# Zigbee_Tracker_v2_Debugger.net
KiCad netlist of a schematic drawn in EAGLE
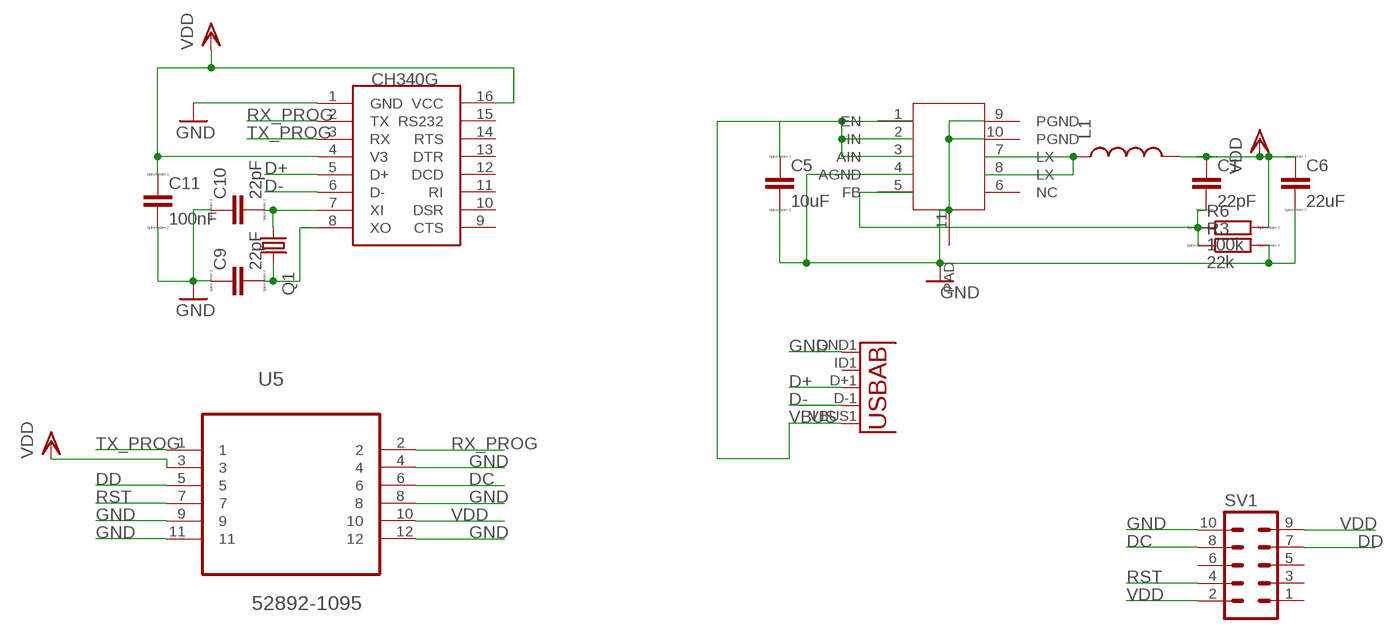
[diagram p0: schematic, sheet 1]

(export (version "E")
  (design (tool "Eeschema 10.0.6"))
  (components
    (comp (ref "C1")
      (value "22pF")
      (footprint "eagle-import:C0402")
      (libsource (lib "eagle-import") (part "CC0402"))
    )
    (comp (ref "C5")
      (value "10uF")
      (footprint "eagle-import:C0402")
      (libsource (lib "eagle-import") (part "CC0402"))
    )
    (comp (ref "C6")
      (value "22uF")
      (footprint "eagle-import:C0402")
      (libsource (lib "eagle-import") (part "CC0402"))
    )
    (comp (ref "C9")
      (value "22pF")
      (footprint "eagle-import:C0402")
      (libsource (lib "eagle-import") (part "CC0402"))
    )
    (comp (ref "C10")
      (value "22pF")
      (footprint "eagle-import:C0402")
      (libsource (lib "eagle-import") (part "CC0402"))
    )
    (comp (ref "C11")
      (value "100nF")
      (footprint "eagle-import:C0402")
      (libsource (lib "eagle-import") (part "CC0402"))
    )
    (comp (ref "L1")
      (value "INDUCTOR")
      (footprint "eagle-import:L0603")
      (libsource (lib "eagle-import") (part "INDUCTOR"))
    )
    (comp (ref "Q1")
      (value "KX-7")
      (footprint "eagle-import:3.2X2.5_KX-7")
      (libsource (lib "eagle-import") (part "KX-7"))
    )
    (comp (ref "R3")
      (value "22k")
      (footprint "eagle-import:R0402")
      (libsource (lib "eagle-import") (part "RR0402"))
    )
    (comp (ref "R6")
      (value "100k")
      (footprint "eagle-import:R0402")
      (libsource (lib "eagle-import") (part "RR0402"))
    )
    (comp (ref "SV1")
      (value "MA05-2")
      (footprint "eagle-import:MA05-2")
      (libsource (lib "eagle-import") (part "MA05-2"))
    )
    (comp (ref "U$1")
      (value "XM5152")
      (footprint "eagle-import:SON50P300X300X80-11T170X240")
      (libsource (lib "eagle-import") (part "XM5152"))
    )
    (comp (ref "U$2")
      (value "CH340G")
      (footprint "eagle-import:SOIC16")
      (libsource (lib "eagle-import") (part "CH340G"))
    )
    (comp (ref "U1")
      (value "USB\"\"")
      (footprint "eagle-import:USB-MICRO-SMD")
      (libsource (lib "eagle-import") (part "USB{dblquote}{dblquote}"))
    )
    (comp (ref "U5")
      (value "52892-1095")
      (footprint "eagle-import:MOLEX_52892-1095")
      (fields (field (name "MF") "Molex"))
      (libsource (lib "eagle-import") (part "52892-1095"))
    )
  )
  (nets
    (net (code "1") (name "/D+") (class "Default")
      (node (ref "U$2") (pin "5") (pinfunction "D+_5") (pintype "bidirectional"))
      (node (ref "U1") (pin "D+1") (pinfunction "D+_D+1") (pintype "bidirectional"))
    )
    (net (code "2") (name "/D-") (class "Default")
      (node (ref "U$2") (pin "6") (pinfunction "D-_6") (pintype "bidirectional"))
      (node (ref "U1") (pin "D-1") (pinfunction "D-_D-1") (pintype "bidirectional"))
    )
    (net (code "3") (name "/DC") (class "Default")
      (node (ref "SV1") (pin "8") (pinfunction "8_8") (pintype "passive"))
      (node (ref "U5") (pin "6") (pinfunction "6_6") (pintype "passive"))
    )
    (net (code "4") (name "/DD") (class "Default")
      (node (ref "SV1") (pin "7") (pinfunction "7_7") (pintype "passive"))
      (node (ref "U5") (pin "5") (pinfunction "5_5") (pintype "passive"))
    )
    (net (code "5") (name "/RST") (class "Default")
      (node (ref "SV1") (pin "4") (pinfunction "4_4") (pintype "passive"))
      (node (ref "U5") (pin "7") (pinfunction "7_7") (pintype "passive"))
    )
    (net (code "6") (name "/RX_PROG") (class "Default")
      (node (ref "U$2") (pin "2") (pinfunction "TX_2") (pintype "bidirectional"))
      (node (ref "U5") (pin "2") (pinfunction "2_2") (pintype "passive"))
    )
    (net (code "7") (name "/TX_PROG") (class "Default")
      (node (ref "U$2") (pin "3") (pinfunction "RX_3") (pintype "bidirectional"))
      (node (ref "U5") (pin "1") (pinfunction "1_1") (pintype "passive"))
    )
    (net (code "8") (name "/VBUS") (class "Default")
      (node (ref "C5") (pin "1") (pinfunction "1_1") (pintype "passive"))
      (node (ref "U$1") (pin "1") (pinfunction "EN_1") (pintype "bidirectional"))
      (node (ref "U$1") (pin "2") (pinfunction "IN_2") (pintype "bidirectional"))
      (node (ref "U$1") (pin "3") (pinfunction "AIN_3") (pintype "bidirectional"))
      (node (ref "U1") (pin "VBUS1") (pinfunction "VBUS_VBUS1") (pintype "bidirectional"))
    )
    (net (code "9") (name "GND") (class "Default")
      (node (ref "C10") (pin "1") (pinfunction "1_1") (pintype "passive"))
      (node (ref "C11") (pin "2") (pinfunction "2_2") (pintype "passive"))
      (node (ref "C5") (pin "2") (pinfunction "2_2") (pintype "passive"))
      (node (ref "C6") (pin "2") (pinfunction "2_2") (pintype "passive"))
      (node (ref "C9") (pin "1") (pinfunction "1_1") (pintype "passive"))
      (node (ref "R3") (pin "2") (pinfunction "2_2") (pintype "passive"))
      (node (ref "SV1") (pin "10") (pinfunction "10_10") (pintype "passive"))
      (node (ref "U$1") (pin "10") (pinfunction "PGND_10") (pintype "bidirectional"))
      (node (ref "U$1") (pin "11") (pinfunction "PAD_11") (pintype "bidirectional"))
      (node (ref "U$1") (pin "4") (pinfunction "AGND_4") (pintype "bidirectional"))
      (node (ref "U$1") (pin "9") (pinfunction "PGND_9") (pintype "bidirectional"))
      (node (ref "U$2") (pin "1") (pinfunction "GND_1") (pintype "bidirectional"))
      (node (ref "U1") (pin "GND1") (pinfunction "GND_GND1") (pintype "bidirectional"))
      (node (ref "U5") (pin "11") (pinfunction "11_11") (pintype "passive"))
      (node (ref "U5") (pin "12") (pinfunction "12_12") (pintype "passive"))
      (node (ref "U5") (pin "4") (pinfunction "4_4") (pintype "passive"))
      (node (ref "U5") (pin "8") (pinfunction "8_8") (pintype "passive"))
      (node (ref "U5") (pin "9") (pinfunction "9_9") (pintype "passive"))
    )
    (net (code "10") (name "Net-(L1-Pad1)") (class "Default")
      (node (ref "L1") (pin "1") (pinfunction "1_1") (pintype "passive"))
      (node (ref "U$1") (pin "7") (pinfunction "LX_7") (pintype "bidirectional"))
      (node (ref "U$1") (pin "8") (pinfunction "LX_8") (pintype "bidirectional"))
    )
    (net (code "11") (name "Net-(Q1-2)") (class "Default")
      (node (ref "C9") (pin "2") (pinfunction "2_2") (pintype "passive"))
      (node (ref "Q1") (pin "3") (pinfunction "2_3") (pintype "passive"))
      (node (ref "U$2") (pin "8") (pinfunction "XO_8") (pintype "bidirectional"))
    )
    (net (code "12") (name "Net-(U$1-FB)") (class "Default")
      (node (ref "C1") (pin "2") (pinfunction "2_2") (pintype "passive"))
      (node (ref "R3") (pin "1") (pinfunction "1_1") (pintype "passive"))
      (node (ref "R6") (pin "1") (pinfunction "1_1") (pintype "passive"))
      (node (ref "U$1") (pin "5") (pinfunction "FB_5") (pintype "bidirectional"))
    )
    (net (code "13") (name "Net-(U$2-XI)") (class "Default")
      (node (ref "C10") (pin "2") (pinfunction "2_2") (pintype "passive"))
      (node (ref "Q1") (pin "1") (pinfunction "1_1") (pintype "passive"))
      (node (ref "U$2") (pin "7") (pinfunction "XI_7") (pintype "bidirectional"))
    )
    (net (code "14") (name "VDD") (class "Default")
      (node (ref "C1") (pin "1") (pinfunction "1_1") (pintype "passive"))
      (node (ref "C11") (pin "1") (pinfunction "1_1") (pintype "passive"))
      (node (ref "C6") (pin "1") (pinfunction "1_1") (pintype "passive"))
      (node (ref "L1") (pin "2") (pinfunction "2_2") (pintype "passive"))
      (node (ref "R6") (pin "2") (pinfunction "2_2") (pintype "passive"))
      (node (ref "SV1") (pin "2") (pinfunction "2_2") (pintype "passive"))
      (node (ref "SV1") (pin "9") (pinfunction "9_9") (pintype "passive"))
      (node (ref "U$2") (pin "16") (pinfunction "VCC_16") (pintype "bidirectional"))
      (node (ref "U$2") (pin "4") (pinfunction "V3_4") (pintype "bidirectional"))
      (node (ref "U5") (pin "10") (pinfunction "10_10") (pintype "passive"))
      (node (ref "U5") (pin "3") (pinfunction "3_3") (pintype "passive"))
    )
    (net (code "15") (name "unconnected-(SV1-Pad1)") (class "Default")
      (node (ref "SV1") (pin "1") (pinfunction "1_1") (pintype "passive"))
    )
    (net (code "16") (name "unconnected-(SV1-Pad3)") (class "Default")
      (node (ref "SV1") (pin "3") (pinfunction "3_3") (pintype "passive"))
    )
    (net (code "17") (name "unconnected-(SV1-Pad5)") (class "Default")
      (node (ref "SV1") (pin "5") (pinfunction "5_5") (pintype "passive"))
    )
    (net (code "18") (name "unconnected-(SV1-Pad6)") (class "Default")
      (node (ref "SV1") (pin "6") (pinfunction "6_6") (pintype "passive"))
    )
    (net (code "19") (name "unconnected-(U$1-NC-Pad6)") (class "Default")
      (node (ref "U$1") (pin "6") (pinfunction "NC_6") (pintype "bidirectional"))
    )
    (net (code "20") (name "unconnected-(U$2-CTS-Pad9)") (class "Default")
      (node (ref "U$2") (pin "9") (pinfunction "CTS_9") (pintype "bidirectional"))
    )
    (net (code "21") (name "unconnected-(U$2-DCD-Pad12)") (class "Default")
      (node (ref "U$2") (pin "12") (pinfunction "DCD_12") (pintype "bidirectional"))
    )
    (net (code "22") (name "unconnected-(U$2-DSR-Pad10)") (class "Default")
      (node (ref "U$2") (pin "10") (pinfunction "DSR_10") (pintype "bidirectional"))
    )
    (net (code "23") (name "unconnected-(U$2-DTR-Pad13)") (class "Default")
      (node (ref "U$2") (pin "13") (pinfunction "DTR_13") (pintype "bidirectional"))
    )
    (net (code "24") (name "unconnected-(U$2-RI-Pad11)") (class "Default")
      (node (ref "U$2") (pin "11") (pinfunction "RI_11") (pintype "bidirectional"))
    )
    (net (code "25") (name "unconnected-(U$2-RS232-Pad15)") (class "Default")
      (node (ref "U$2") (pin "15") (pinfunction "RS232_15") (pintype "bidirectional"))
    )
    (net (code "26") (name "unconnected-(U$2-RTS-Pad14)") (class "Default")
      (node (ref "U$2") (pin "14") (pinfunction "RTS_14") (pintype "bidirectional"))
    )
    (net (code "27") (name "unconnected-(U1-USBID-PadID1)") (class "Default")
      (node (ref "U1") (pin "ID1") (pinfunction "USBID_ID1") (pintype "bidirectional"))
    )
  )
)
